# Adafruit_1_2inch_8x8_backpack.net
KiCad netlist of a schematic drawn in EAGLE
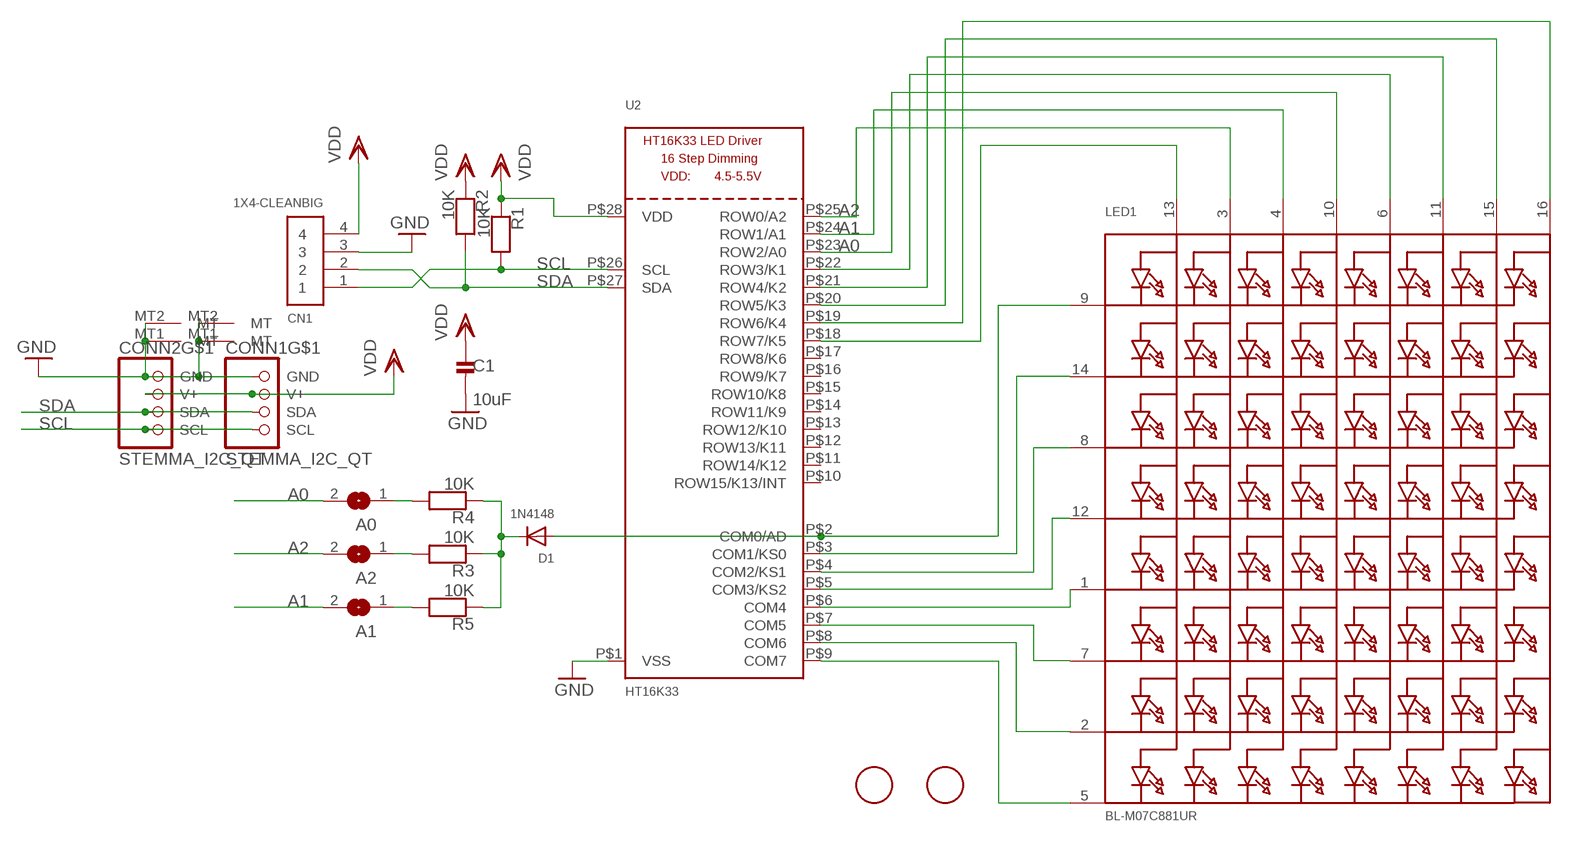
[diagram p0: schematic, sheet 1]

(export (version "E")
  (design (tool "Eeschema 10.0.6"))
  (components
    (comp (ref "A0")
      (value "SOLDERJUMPERREFLOW_NOPASTE")
      (footprint "eagle-import:SOLDERJUMPER_REFLOW_NOPASTE")
      (libsource (lib "eagle-import") (part "SOLDERJUMPERREFLOW_NOPASTE"))
    )
    (comp (ref "A1")
      (value "SOLDERJUMPERREFLOW_NOPASTE")
      (footprint "eagle-import:SOLDERJUMPER_REFLOW_NOPASTE")
      (libsource (lib "eagle-import") (part "SOLDERJUMPERREFLOW_NOPASTE"))
    )
    (comp (ref "A2")
      (value "SOLDERJUMPERREFLOW_NOPASTE")
      (footprint "eagle-import:SOLDERJUMPER_REFLOW_NOPASTE")
      (libsource (lib "eagle-import") (part "SOLDERJUMPERREFLOW_NOPASTE"))
    )
    (comp (ref "C1")
      (value "10uF")
      (footprint "eagle-import:0805-NO")
      (libsource (lib "eagle-import") (part "CAP_CERAMIC0805-NOOUTLINE"))
    )
    (comp (ref "CN1")
      (value "1X4-CLEANBIG")
      (footprint "eagle-import:1X04-CLEANBIG")
      (libsource (lib "eagle-import") (part "1X4-CLEANBIG"))
    )
    (comp (ref "CONN1")
      (value "STEMMA_I2C_QT")
      (footprint "eagle-import:JST_SH4")
      (libsource (lib "eagle-import") (part "STEMMA_I2C_QT"))
    )
    (comp (ref "CONN2")
      (value "STEMMA_I2C_QT")
      (footprint "eagle-import:JST_SH4")
      (libsource (lib "eagle-import") (part "STEMMA_I2C_QT"))
    )
    (comp (ref "D1")
      (value "1N4148")
      (footprint "eagle-import:SOD-323")
      (libsource (lib "eagle-import") (part "DIODESOD-323"))
    )
    (comp (ref "LED1")
      (value "BL-M07C881UR")
      (footprint "eagle-import:SEGMENT_BL-M12A881UR")
      (libsource (lib "eagle-import") (part "DISP_SEGMENT_8X8_ROWCATHODEM12A881UR"))
    )
    (comp (ref "R1")
      (value "10K")
      (footprint "eagle-import:0603-NO")
      (libsource (lib "eagle-import") (part "RESISTOR_0603_NOOUT"))
    )
    (comp (ref "R2")
      (value "10K")
      (footprint "eagle-import:0603-NO")
      (libsource (lib "eagle-import") (part "RESISTOR_0603_NOOUT"))
    )
    (comp (ref "R3")
      (value "10K")
      (footprint "eagle-import:0603-NO")
      (libsource (lib "eagle-import") (part "RESISTOR_0603_NOOUT"))
    )
    (comp (ref "R4")
      (value "10K")
      (footprint "eagle-import:0603-NO")
      (libsource (lib "eagle-import") (part "RESISTOR_0603_NOOUT"))
    )
    (comp (ref "R5")
      (value "10K")
      (footprint "eagle-import:0603-NO")
      (libsource (lib "eagle-import") (part "RESISTOR_0603_NOOUT"))
    )
    (comp (ref "U$1")
      (value "FIDUCIAL")
      (footprint "eagle-import:FIDUCIAL_1MM")
      (libsource (lib "eagle-import") (part "FIDUCIAL"))
    )
    (comp (ref "U$2")
      (value "FIDUCIAL")
      (footprint "eagle-import:FIDUCIAL_1MM")
      (libsource (lib "eagle-import") (part "FIDUCIAL"))
    )
    (comp (ref "U2")
      (value "HT16K33")
      (footprint "eagle-import:SOP28_300MIL")
      (libsource (lib "eagle-import") (part "HT16K33_SOP28"))
    )
  )
  (nets
    (net (code "1") (name "/A0") (class "Default")
      (node (ref "A0") (pin "2") (pinfunction "2_2") (pintype "passive"))
      (node (ref "LED1") (pin "10") (pinfunction "A4_10") (pintype "bidirectional"))
      (node (ref "U2") (pin "P$23") (pinfunction "ROW2/A0_P$23") (pintype "bidirectional"))
    )
    (net (code "2") (name "/A1") (class "Default")
      (node (ref "A1") (pin "2") (pinfunction "2_2") (pintype "passive"))
      (node (ref "LED1") (pin "4") (pinfunction "A3_4") (pintype "bidirectional"))
      (node (ref "U2") (pin "P$24") (pinfunction "ROW1/A1_P$24") (pintype "bidirectional"))
    )
    (net (code "3") (name "/A2") (class "Default")
      (node (ref "A2") (pin "2") (pinfunction "2_2") (pintype "passive"))
      (node (ref "LED1") (pin "3") (pinfunction "A2_3") (pintype "bidirectional"))
      (node (ref "U2") (pin "P$25") (pinfunction "ROW0/A2_P$25") (pintype "bidirectional"))
    )
    (net (code "4") (name "/SCL") (class "Default")
      (node (ref "CN1") (pin "1") (pinfunction "1_1") (pintype "bidirectional"))
      (node (ref "CONN1") (pin "4") (pinfunction "SCL_4") (pintype "passive"))
      (node (ref "CONN2") (pin "4") (pinfunction "SCL_4") (pintype "passive"))
      (node (ref "R1") (pin "2") (pinfunction "2_2") (pintype "passive"))
      (node (ref "U2") (pin "P$26") (pinfunction "SCL_P$26") (pintype "bidirectional"))
    )
    (net (code "5") (name "/SDA") (class "Default")
      (node (ref "CN1") (pin "2") (pinfunction "2_2") (pintype "bidirectional"))
      (node (ref "CONN1") (pin "3") (pinfunction "SDA_3") (pintype "passive"))
      (node (ref "CONN2") (pin "3") (pinfunction "SDA_3") (pintype "passive"))
      (node (ref "R2") (pin "2") (pinfunction "2_2") (pintype "passive"))
      (node (ref "U2") (pin "P$27") (pinfunction "SDA_P$27") (pintype "bidirectional"))
    )
    (net (code "6") (name "GND") (class "Default")
      (node (ref "C1") (pin "2") (pinfunction "2_2") (pintype "passive"))
      (node (ref "CN1") (pin "3") (pinfunction "3_3") (pintype "bidirectional"))
      (node (ref "CONN1") (pin "1") (pinfunction "GND_1") (pintype "passive"))
      (node (ref "CONN1") (pin "MT1") (pinfunction "MT_MT1") (pintype "bidirectional"))
      (node (ref "CONN1") (pin "MT2") (pinfunction "MT_MT2") (pintype "bidirectional"))
      (node (ref "CONN2") (pin "1") (pinfunction "GND_1") (pintype "passive"))
      (node (ref "CONN2") (pin "MT1") (pinfunction "MT_MT1") (pintype "bidirectional"))
      (node (ref "CONN2") (pin "MT2") (pinfunction "MT_MT2") (pintype "bidirectional"))
      (node (ref "U2") (pin "P$1") (pinfunction "VSS_P$1") (pintype "bidirectional"))
    )
    (net (code "7") (name "Net-(A0-Pad1)") (class "Default")
      (node (ref "A0") (pin "1") (pinfunction "1_1") (pintype "passive"))
      (node (ref "R4") (pin "2") (pinfunction "2_2") (pintype "passive"))
    )
    (net (code "8") (name "Net-(A1-Pad1)") (class "Default")
      (node (ref "A1") (pin "1") (pinfunction "1_1") (pintype "passive"))
      (node (ref "R5") (pin "2") (pinfunction "2_2") (pintype "passive"))
    )
    (net (code "9") (name "Net-(A2-Pad1)") (class "Default")
      (node (ref "A2") (pin "1") (pinfunction "1_1") (pintype "passive"))
      (node (ref "R3") (pin "2") (pinfunction "2_2") (pintype "passive"))
    )
    (net (code "10") (name "Net-(D1-PadC)") (class "Default")
      (node (ref "D1") (pin "C") (pinfunction "C_C") (pintype "passive"))
      (node (ref "R3") (pin "1") (pinfunction "1_1") (pintype "passive"))
      (node (ref "R4") (pin "1") (pinfunction "1_1") (pintype "passive"))
      (node (ref "R5") (pin "1") (pinfunction "1_1") (pintype "passive"))
    )
    (net (code "11") (name "Net-(LED1-A1)") (class "Default")
      (node (ref "LED1") (pin "13") (pinfunction "A1_13") (pintype "bidirectional"))
      (node (ref "U2") (pin "P$18") (pinfunction "ROW7/K5_P$18") (pintype "bidirectional"))
    )
    (net (code "12") (name "Net-(LED1-A5)") (class "Default")
      (node (ref "LED1") (pin "6") (pinfunction "A5_6") (pintype "bidirectional"))
      (node (ref "U2") (pin "P$22") (pinfunction "ROW3/K1_P$22") (pintype "bidirectional"))
    )
    (net (code "13") (name "Net-(LED1-A6)") (class "Default")
      (node (ref "LED1") (pin "11") (pinfunction "A6_11") (pintype "bidirectional"))
      (node (ref "U2") (pin "P$21") (pinfunction "ROW4/K2_P$21") (pintype "bidirectional"))
    )
    (net (code "14") (name "Net-(LED1-A7)") (class "Default")
      (node (ref "LED1") (pin "15") (pinfunction "A7_15") (pintype "bidirectional"))
      (node (ref "U2") (pin "P$20") (pinfunction "ROW5/K3_P$20") (pintype "bidirectional"))
    )
    (net (code "15") (name "Net-(LED1-A8)") (class "Default")
      (node (ref "LED1") (pin "16") (pinfunction "A8_16") (pintype "bidirectional"))
      (node (ref "U2") (pin "P$19") (pinfunction "ROW6/K4_P$19") (pintype "bidirectional"))
    )
    (net (code "16") (name "Net-(LED1-K1)") (class "Default")
      (node (ref "D1") (pin "A") (pinfunction "A_A") (pintype "passive"))
      (node (ref "LED1") (pin "9") (pinfunction "K1_9") (pintype "bidirectional"))
      (node (ref "U2") (pin "P$2") (pinfunction "COM0/AD_P$2") (pintype "bidirectional"))
    )
    (net (code "17") (name "Net-(LED1-K2)") (class "Default")
      (node (ref "LED1") (pin "14") (pinfunction "K2_14") (pintype "bidirectional"))
      (node (ref "U2") (pin "P$3") (pinfunction "COM1/KS0_P$3") (pintype "bidirectional"))
    )
    (net (code "18") (name "Net-(LED1-K3)") (class "Default")
      (node (ref "LED1") (pin "8") (pinfunction "K3_8") (pintype "bidirectional"))
      (node (ref "U2") (pin "P$4") (pinfunction "COM2/KS1_P$4") (pintype "bidirectional"))
    )
    (net (code "19") (name "Net-(LED1-K4)") (class "Default")
      (node (ref "LED1") (pin "12") (pinfunction "K4_12") (pintype "bidirectional"))
      (node (ref "U2") (pin "P$5") (pinfunction "COM3/KS2_P$5") (pintype "bidirectional"))
    )
    (net (code "20") (name "Net-(LED1-K5)") (class "Default")
      (node (ref "LED1") (pin "1") (pinfunction "K5_1") (pintype "bidirectional"))
      (node (ref "U2") (pin "P$6") (pinfunction "COM4_P$6") (pintype "bidirectional"))
    )
    (net (code "21") (name "Net-(LED1-K6)") (class "Default")
      (node (ref "LED1") (pin "7") (pinfunction "K6_7") (pintype "bidirectional"))
      (node (ref "U2") (pin "P$7") (pinfunction "COM5_P$7") (pintype "bidirectional"))
    )
    (net (code "22") (name "Net-(LED1-K7)") (class "Default")
      (node (ref "LED1") (pin "2") (pinfunction "K7_2") (pintype "bidirectional"))
      (node (ref "U2") (pin "P$8") (pinfunction "COM6_P$8") (pintype "bidirectional"))
    )
    (net (code "23") (name "Net-(LED1-K8)") (class "Default")
      (node (ref "LED1") (pin "5") (pinfunction "K8_5") (pintype "bidirectional"))
      (node (ref "U2") (pin "P$9") (pinfunction "COM7_P$9") (pintype "bidirectional"))
    )
    (net (code "24") (name "VDD") (class "Default")
      (node (ref "C1") (pin "1") (pinfunction "1_1") (pintype "passive"))
      (node (ref "CN1") (pin "4") (pinfunction "4_4") (pintype "bidirectional"))
      (node (ref "CONN1") (pin "2") (pinfunction "V+_2") (pintype "passive"))
      (node (ref "CONN2") (pin "2") (pinfunction "V+_2") (pintype "passive"))
      (node (ref "R1") (pin "1") (pinfunction "1_1") (pintype "passive"))
      (node (ref "R2") (pin "1") (pinfunction "1_1") (pintype "passive"))
      (node (ref "U2") (pin "P$28") (pinfunction "VDD_P$28") (pintype "bidirectional"))
    )
    (net (code "25") (name "unconnected-(U2-ROW8{slash}K6-PadP$17)") (class "Default")
      (node (ref "U2") (pin "P$17") (pinfunction "ROW8/K6_P$17") (pintype "bidirectional"))
    )
    (net (code "26") (name "unconnected-(U2-ROW9{slash}K7-PadP$16)") (class "Default")
      (node (ref "U2") (pin "P$16") (pinfunction "ROW9/K7_P$16") (pintype "bidirectional"))
    )
    (net (code "27") (name "unconnected-(U2-ROW10{slash}K8-PadP$15)") (class "Default")
      (node (ref "U2") (pin "P$15") (pinfunction "ROW10/K8_P$15") (pintype "bidirectional"))
    )
    (net (code "28") (name "unconnected-(U2-ROW11{slash}K9-PadP$14)") (class "Default")
      (node (ref "U2") (pin "P$14") (pinfunction "ROW11/K9_P$14") (pintype "bidirectional"))
    )
    (net (code "29") (name "unconnected-(U2-ROW12{slash}K10-PadP$13)") (class "Default")
      (node (ref "U2") (pin "P$13") (pinfunction "ROW12/K10_P$13") (pintype "bidirectional"))
    )
    (net (code "30") (name "unconnected-(U2-ROW13{slash}K11-PadP$12)") (class "Default")
      (node (ref "U2") (pin "P$12") (pinfunction "ROW13/K11_P$12") (pintype "bidirectional"))
    )
    (net (code "31") (name "unconnected-(U2-ROW14{slash}K12-PadP$11)") (class "Default")
      (node (ref "U2") (pin "P$11") (pinfunction "ROW14/K12_P$11") (pintype "bidirectional"))
    )
    (net (code "32") (name "unconnected-(U2-ROW15{slash}K13{slash}INT-PadP$10)") (class "Default")
      (node (ref "U2") (pin "P$10") (pinfunction "ROW15/K13/INT_P$10") (pintype "bidirectional"))
    )
  )
)
